# EFR_IO_Connections.net
KiCad netlist of a schematic drawn in Altium Designer
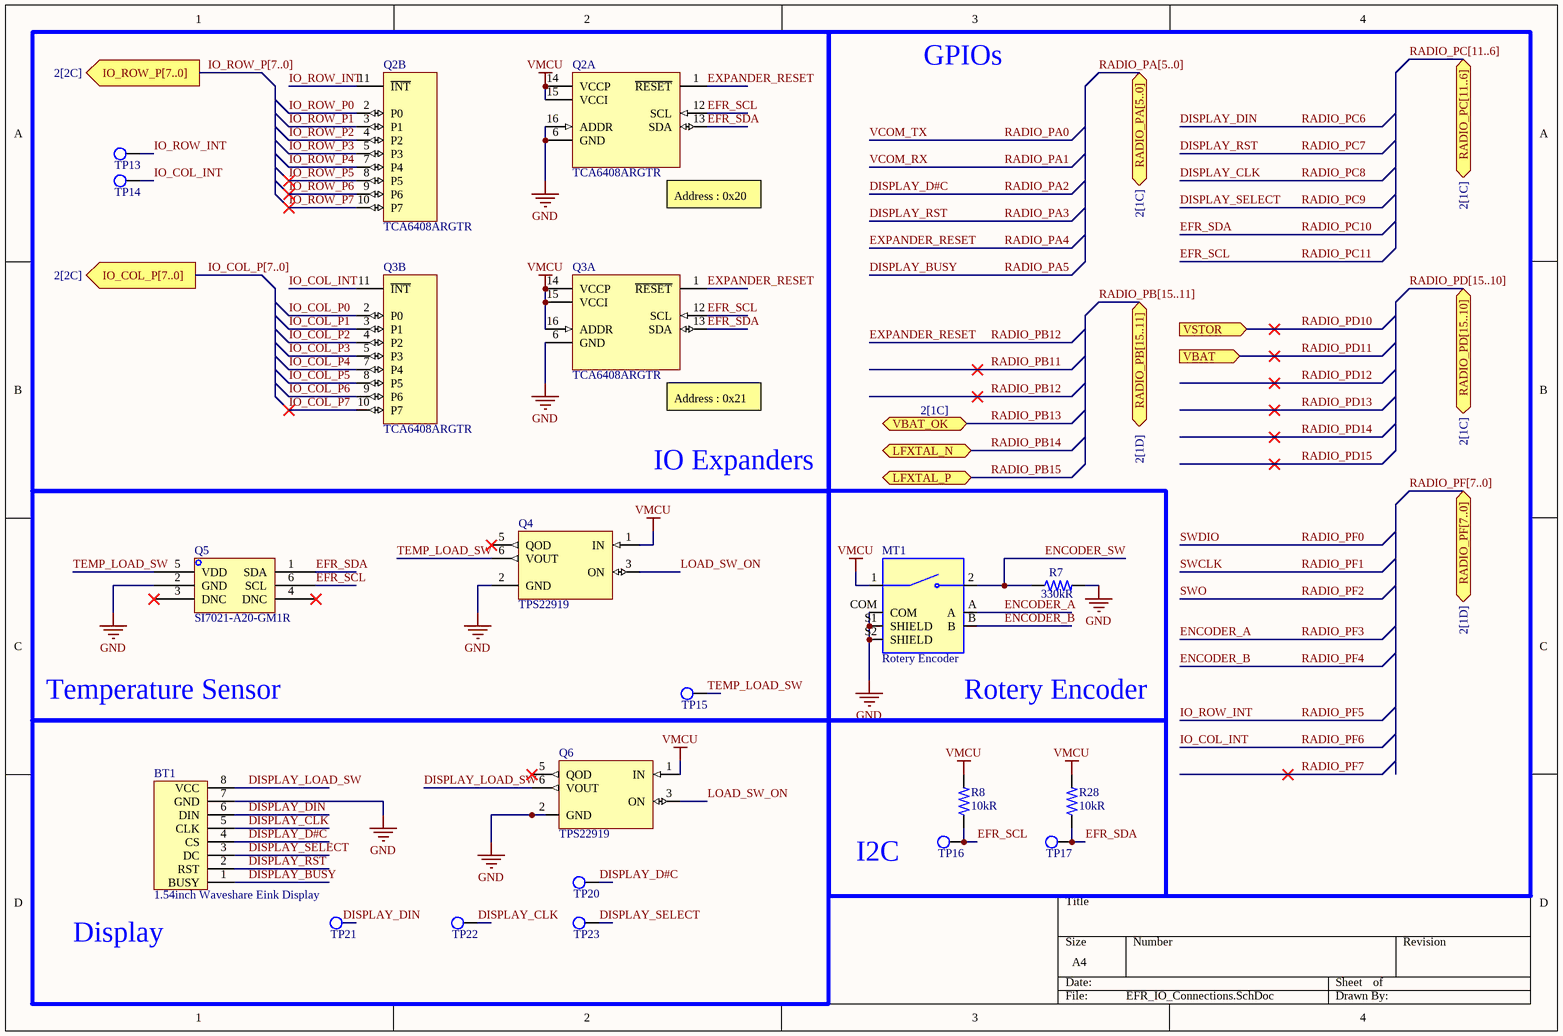
[diagram p0: EFR_IO_Connections.SchDoc]

(export (version "E")
  (design (tool "Eeschema 10.0.6"))
  (components
    (comp (ref "BT1")
      (value "1.54inch Waveshare Eink Display")
      (footprint "1.54inch waveshare eink")
      (libsource (lib "Keyboard_parts") (part "1.54inch Waveshare Eink Display"))
    )
    (comp (ref "MT1")
      (value "Rotery Encoder")
      (footprint "Rotery Encoder")
      (description "Rotary Position Encoder, Single, 2 Channels")
      (fields (field (name "MP") "PEC11R-4215F-S0024") (field (name "MANUFACTURER") "Bourns"))
      (libsource (lib "InsaneIntegratedLib") (part "Rotery Encoder"))
    )
    (comp (ref "Q2")
      (value "TCA6408ARGTR")
      (footprint "TCA6408ARGTR - IO Expander")
      (description "Parallel I/O Port, 8-Bit, 8 I/O, CMOS, PQCC16")
      (fields (field (name "MANUFACTURER") "Texas Instruments"))
      (libsource (lib "Keyboard_parts") (part "TCA6408ARGTR"))
    )
    (comp (ref "Q3")
      (value "TCA6408ARGTR")
      (footprint "TCA6408ARGTR - IO Expander")
      (description "Parallel I/O Port, 8-Bit, 8 I/O, CMOS, PQCC16")
      (fields (field (name "MANUFACTURER") "Texas Instruments"))
      (libsource (lib "Keyboard_parts") (part "TCA6408ARGTR"))
    )
    (comp (ref "Q4")
      (value "TPS22919")
      (footprint "TPS22919DCKR - Load SW")
      (description "Buffer/Inverter Based Peripheral Driver, 3A, PDSO6")
      (fields
        (field (name "MANUFACTURER") "Texas Instruments")
        (field (name "MANUFACTURER PART NUMBER") "TPS22919DCKT")
      )
      (libsource (lib "Keyboard_parts") (part "TPS22919"))
    )
    (comp (ref "Q5")
      (value "SI7021-A20-GM1R")
      (footprint "Si7021-A20 - Temp")
      (description "Serial Switch/Digital Sensor, 14 Bit(s), 0.40Cel, Square, Surface Mount")
      (fields (field (name "MANUFACTURER") "Silicon Labs"))
      (libsource (lib "Keyboard_parts") (part "SI7021-A20-GM1R"))
    )
    (comp (ref "Q6")
      (value "TPS22919")
      (footprint "TPS22919DCKR - Load SW")
      (description "Buffer/Inverter Based Peripheral Driver, 3A, PDSO6")
      (fields
        (field (name "MANUFACTURER") "Texas Instruments")
        (field (name "MANUFACTURER PART NUMBER") "TPS22919DCKT")
      )
      (libsource (lib "Keyboard_parts") (part "TPS22919"))
    )
    (comp (ref "R7")
      (value "330kR")
      (footprint "Resistor 0603")
      (fields
        (field (name "MANUFACTURER") "Yageo")
        (field (name "MANUFACTURER PART NUMBER") "RC0603JR-07330KL")
        (field (name "TOLERANCE") "5%")
      )
      (libsource (lib "Keyboard_parts") (part "RES 330K 0603"))
    )
    (comp (ref "R8")
      (value "10kR")
      (footprint "Resistor 0603")
      (fields
        (field (name "MANUFACTURER") "Yageo")
        (field (name "MANUFACTURER PART NUMBER") "RC0603FR-0710KL")
        (field (name "TOLERANCE") "1%")
      )
      (libsource (lib "Keyboard_parts") (part "RES 10K 0603"))
    )
    (comp (ref "R28")
      (value "10kR")
      (footprint "Resistor 0603")
      (fields
        (field (name "MANUFACTURER") "Yageo")
        (field (name "MANUFACTURER PART NUMBER") "RC0603FR-0710KL")
        (field (name "TOLERANCE") "1%")
      )
      (libsource (lib "Keyboard_parts") (part "RES 10K 0603"))
    )
    (comp (ref "TP13")
      (value "Test point")
      (footprint "Test Point")
      (libsource (lib "Keyboard_parts") (part "Test point"))
    )
    (comp (ref "TP14")
      (value "Test point")
      (footprint "Test Point")
      (libsource (lib "Keyboard_parts") (part "Test point"))
    )
    (comp (ref "TP15")
      (value "Test point")
      (footprint "Test Point")
      (libsource (lib "Keyboard_parts") (part "Test point"))
    )
    (comp (ref "TP16")
      (value "Test point")
      (footprint "Test Point")
      (libsource (lib "Keyboard_parts") (part "Test point"))
    )
    (comp (ref "TP17")
      (value "Test point")
      (footprint "Test Point")
      (libsource (lib "Keyboard_parts") (part "Test point"))
    )
    (comp (ref "TP20")
      (value "Test point")
      (footprint "Test Point")
      (libsource (lib "Keyboard_parts") (part "Test point"))
    )
    (comp (ref "TP21")
      (value "Test point")
      (footprint "Test Point")
      (libsource (lib "Keyboard_parts") (part "Test point"))
    )
    (comp (ref "TP22")
      (value "Test point")
      (footprint "Test Point")
      (libsource (lib "Keyboard_parts") (part "Test point"))
    )
    (comp (ref "TP23")
      (value "Test point")
      (footprint "Test Point")
      (libsource (lib "Keyboard_parts") (part "Test point"))
    )
  )
  (nets
    (net (code "1") (name "/DISPLAY_LOAD_SW") (class "Default")
      (node (ref "BT1") (pin "8") (pinfunction "VCC_8") (pintype "passive"))
      (node (ref "Q6") (pin "6") (pinfunction "VOUT_6") (pintype "output"))
    )
    (net (code "2") (name "/ENCODER_SW") (class "Default")
      (node (ref "MT1") (pin "2") (pinfunction "2_2") (pintype "passive"))
      (node (ref "R7") (pin "1") (pinfunction "1_1") (pintype "passive"))
    )
    (net (code "3") (name "/IO_COL_P0") (class "Default")
      (node (ref "Q3") (pin "2") (pinfunction "P0_2") (pintype "bidirectional"))
    )
    (net (code "4") (name "/IO_COL_P1") (class "Default")
      (node (ref "Q3") (pin "3") (pinfunction "P1_3") (pintype "bidirectional"))
    )
    (net (code "5") (name "/IO_COL_P2") (class "Default")
      (node (ref "Q3") (pin "4") (pinfunction "P2_4") (pintype "bidirectional"))
    )
    (net (code "6") (name "/IO_COL_P3") (class "Default")
      (node (ref "Q3") (pin "5") (pinfunction "P3_5") (pintype "bidirectional"))
    )
    (net (code "7") (name "/IO_COL_P4") (class "Default")
      (node (ref "Q3") (pin "7") (pinfunction "P4_7") (pintype "bidirectional"))
    )
    (net (code "8") (name "/IO_COL_P5") (class "Default")
      (node (ref "Q3") (pin "8") (pinfunction "P5_8") (pintype "bidirectional"))
    )
    (net (code "9") (name "/IO_COL_P6") (class "Default")
      (node (ref "Q3") (pin "9") (pinfunction "P6_9") (pintype "bidirectional"))
    )
    (net (code "10") (name "/IO_COL_P7") (class "Default")
      (node (ref "Q3") (pin "10") (pinfunction "P7_10") (pintype "bidirectional+no_connect"))
    )
    (net (code "12") (name "/IO_ROW_P0") (class "Default")
      (node (ref "Q2") (pin "2") (pinfunction "P0_2") (pintype "bidirectional"))
    )
    (net (code "13") (name "/IO_ROW_P1") (class "Default")
      (node (ref "Q2") (pin "3") (pinfunction "P1_3") (pintype "bidirectional"))
    )
    (net (code "14") (name "/IO_ROW_P2") (class "Default")
      (node (ref "Q2") (pin "4") (pinfunction "P2_4") (pintype "bidirectional"))
    )
    (net (code "15") (name "/IO_ROW_P3") (class "Default")
      (node (ref "Q2") (pin "5") (pinfunction "P3_5") (pintype "bidirectional"))
    )
    (net (code "16") (name "/IO_ROW_P4") (class "Default")
      (node (ref "Q2") (pin "7") (pinfunction "P4_7") (pintype "bidirectional"))
    )
    (net (code "17") (name "/IO_ROW_P5") (class "Default")
      (node (ref "Q2") (pin "8") (pinfunction "P5_8") (pintype "bidirectional+no_connect"))
    )
    (net (code "18") (name "/IO_ROW_P6") (class "Default")
      (node (ref "Q2") (pin "9") (pinfunction "P6_9") (pintype "bidirectional+no_connect"))
    )
    (net (code "19") (name "/IO_ROW_P7") (class "Default")
      (node (ref "Q2") (pin "10") (pinfunction "P7_10") (pintype "bidirectional+no_connect"))
    )
    (net (code "21") (name "/LOAD_SW_ON") (class "Default")
      (node (ref "Q4") (pin "3") (pinfunction "ON_3") (pintype "bidirectional"))
      (node (ref "Q6") (pin "3") (pinfunction "ON_3") (pintype "bidirectional"))
    )
    (net (code "24") (name "/RADIO_PA2") (class "Default")
      (node (ref "BT1") (pin "4") (pinfunction "CS_4") (pintype "passive"))
      (node (ref "TP20") (pin "1") (pinfunction "1_1") (pintype "passive"))
    )
    (net (code "25") (name "/RADIO_PA5") (class "Default")
      (node (ref "BT1") (pin "1") (pinfunction "BUSY_1") (pintype "passive"))
    )
    (net (code "28") (name "/RADIO_PB12") (class "Default")
      (node (ref "Q2") (pin "1") (pinfunction "~{RESET}_1") (pintype "passive"))
      (node (ref "Q3") (pin "1") (pinfunction "~{RESET}_1") (pintype "passive"))
    )
    (net (code "33") (name "/RADIO_PC6") (class "Default")
      (node (ref "BT1") (pin "6") (pinfunction "DIN_6") (pintype "passive"))
      (node (ref "TP21") (pin "1") (pinfunction "1_1") (pintype "passive"))
    )
    (net (code "34") (name "/RADIO_PC7") (class "Default")
      (node (ref "BT1") (pin "2") (pinfunction "RST_2") (pintype "passive"))
    )
    (net (code "35") (name "/RADIO_PC8") (class "Default")
      (node (ref "BT1") (pin "5") (pinfunction "CLK_5") (pintype "passive"))
      (node (ref "TP22") (pin "1") (pinfunction "1_1") (pintype "passive"))
    )
    (net (code "36") (name "/RADIO_PC9") (class "Default")
      (node (ref "BT1") (pin "3") (pinfunction "DC_3") (pintype "passive"))
      (node (ref "TP23") (pin "1") (pinfunction "1_1") (pintype "passive"))
    )
    (net (code "37") (name "/RADIO_PC10") (class "Default")
      (node (ref "Q2") (pin "13") (pinfunction "SDA_13") (pintype "bidirectional"))
      (node (ref "Q3") (pin "13") (pinfunction "SDA_13") (pintype "bidirectional"))
      (node (ref "Q5") (pin "1") (pinfunction "SDA_1") (pintype "passive"))
      (node (ref "R28") (pin "1") (pinfunction "1_1") (pintype "passive"))
      (node (ref "TP17") (pin "1") (pinfunction "1_1") (pintype "passive"))
    )
    (net (code "38") (name "/RADIO_PC11") (class "Default")
      (node (ref "Q2") (pin "12") (pinfunction "SCL_12") (pintype "input"))
      (node (ref "Q3") (pin "12") (pinfunction "SCL_12") (pintype "input"))
      (node (ref "Q5") (pin "6") (pinfunction "SCL_6") (pintype "passive"))
      (node (ref "R8") (pin "1") (pinfunction "1_1") (pintype "passive"))
      (node (ref "TP16") (pin "1") (pinfunction "1_1") (pintype "passive"))
    )
    (net (code "50") (name "/RADIO_PF3") (class "Default")
      (node (ref "MT1") (pin "A") (pinfunction "A_A") (pintype "passive"))
    )
    (net (code "51") (name "/RADIO_PF4") (class "Default")
      (node (ref "MT1") (pin "B") (pinfunction "B_B") (pintype "passive"))
    )
    (net (code "52") (name "/RADIO_PF5") (class "Default")
      (node (ref "Q2") (pin "11") (pinfunction "~{INT}_11") (pintype "passive"))
      (node (ref "TP13") (pin "1") (pinfunction "1_1") (pintype "passive"))
    )
    (net (code "53") (name "/RADIO_PF6") (class "Default")
      (node (ref "Q3") (pin "11") (pinfunction "~{INT}_11") (pintype "passive"))
      (node (ref "TP14") (pin "1") (pinfunction "1_1") (pintype "passive"))
    )
    (net (code "56") (name "/TEMP_LOAD_SW") (class "Default")
      (node (ref "Q4") (pin "6") (pinfunction "VOUT_6") (pintype "output"))
      (node (ref "Q5") (pin "5") (pinfunction "VDD_5") (pintype "passive"))
      (node (ref "TP15") (pin "1") (pinfunction "1_1") (pintype "passive"))
    )
    (net (code "57") (name "GND") (class "Default")
      (node (ref "BT1") (pin "7") (pinfunction "GND_7") (pintype "passive"))
      (node (ref "MT1") (pin "COM") (pinfunction "COM_COM") (pintype "passive"))
      (node (ref "MT1") (pin "S1") (pinfunction "SHIELD_S1") (pintype "passive"))
      (node (ref "MT1") (pin "S2") (pinfunction "SHIELD_S2") (pintype "passive"))
      (node (ref "Q2") (pin "16") (pinfunction "ADDR_16") (pintype "input"))
      (node (ref "Q2") (pin "6") (pinfunction "GND_6") (pintype "passive"))
      (node (ref "Q3") (pin "6") (pinfunction "GND_6") (pintype "passive"))
      (node (ref "Q4") (pin "2") (pinfunction "GND_2") (pintype "passive"))
      (node (ref "Q5") (pin "2") (pinfunction "GND_2") (pintype "passive"))
      (node (ref "Q6") (pin "2") (pinfunction "GND_2") (pintype "passive"))
      (node (ref "R7") (pin "2") (pinfunction "2_2") (pintype "passive"))
    )
    (net (code "58") (name "VMCU") (class "Default")
      (node (ref "MT1") (pin "1") (pinfunction "1_1") (pintype "passive"))
      (node (ref "Q2") (pin "14") (pinfunction "VCCP_14") (pintype "power_in"))
      (node (ref "Q2") (pin "15") (pinfunction "VCCI_15") (pintype "power_in"))
      (node (ref "Q3") (pin "14") (pinfunction "VCCP_14") (pintype "power_in"))
      (node (ref "Q3") (pin "15") (pinfunction "VCCI_15") (pintype "power_in"))
      (node (ref "Q3") (pin "16") (pinfunction "ADDR_16") (pintype "input"))
      (node (ref "Q4") (pin "1") (pinfunction "IN_1") (pintype "input"))
      (node (ref "Q6") (pin "1") (pinfunction "IN_1") (pintype "input"))
      (node (ref "R28") (pin "2") (pinfunction "2_2") (pintype "passive"))
      (node (ref "R8") (pin "2") (pinfunction "2_2") (pintype "passive"))
    )
    (net (code "59") (name "unconnected-(Q4-QOD-Pad5)") (class "Default")
      (node (ref "Q4") (pin "5") (pinfunction "QOD_5") (pintype "output+no_connect"))
    )
    (net (code "60") (name "unconnected-(Q5-DNC-Pad3)") (class "Default")
      (node (ref "Q5") (pin "3") (pinfunction "DNC_3") (pintype "passive+no_connect"))
    )
    (net (code "61") (name "unconnected-(Q5-DNC-Pad4)") (class "Default")
      (node (ref "Q5") (pin "4") (pinfunction "DNC_4") (pintype "passive+no_connect"))
    )
    (net (code "62") (name "unconnected-(Q6-QOD-Pad5)") (class "Default")
      (node (ref "Q6") (pin "5") (pinfunction "QOD_5") (pintype "output+no_connect"))
    )
  )
)
